# LED_KEYBOARD.net
KiCad netlist of a schematic drawn in Altium Designer
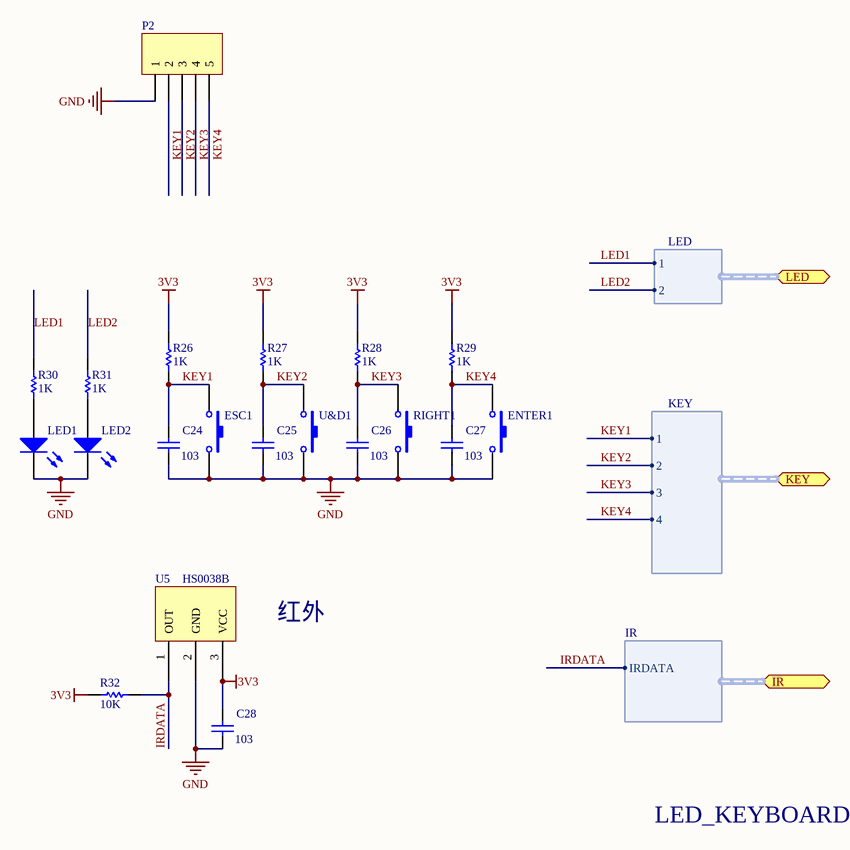
[diagram p0: LED_KEYBOARD.SchDoc]

(export (version "E")
  (design (tool "Eeschema 10.0.6"))
  (components
    (comp (ref "C24")
      (value "103")
      (footprint "RC0805")
      (description "Capacitor")
      (fields (field (name "Comment") "Cap") (field (name "PUBLISHER") "Altium Limited"))
      (libsource (lib "Miscellaneous Devices") (part "Cap"))
    )
    (comp (ref "C25")
      (value "103")
      (footprint "RC0805")
      (description "Capacitor")
      (fields (field (name "Comment") "Cap") (field (name "PUBLISHER") "Altium Limited"))
      (libsource (lib "Miscellaneous Devices") (part "Cap"))
    )
    (comp (ref "C26")
      (value "103")
      (footprint "RC0805")
      (description "Capacitor")
      (fields (field (name "Comment") "Cap") (field (name "PUBLISHER") "Altium Limited"))
      (libsource (lib "Miscellaneous Devices") (part "Cap"))
    )
    (comp (ref "C27")
      (value "103")
      (footprint "RC0805")
      (description "Capacitor")
      (fields (field (name "Comment") "Cap") (field (name "PUBLISHER") "Altium Limited"))
      (libsource (lib "Miscellaneous Devices") (part "Cap"))
    )
    (comp (ref "C28")
      (value "103")
      (footprint "RC0805")
      (description "Capacitor")
      (fields (field (name "Comment") "Cap") (field (name "PUBLISHER") "Altium Limited"))
      (libsource (lib "Miscellaneous Devices") (part "Cap"))
    )
    (comp (ref "ENTER1")
      (value "SW-PB")
      (footprint "KEY6*6(LARGE)")
      (description "Switch")
      (fields (field (name "PUBLISHER") "Altium Limited"))
      (libsource (lib "Miscellaneous Devices") (part "SW-PB"))
    )
    (comp (ref "ESC1")
      (value "SW-PB")
      (footprint "KEY6*6(LARGE)")
      (description "Switch")
      (fields (field (name "PUBLISHER") "Altium Limited"))
      (libsource (lib "Miscellaneous Devices") (part "SW-PB"))
    )
    (comp (ref "LED1")
      (value "LED0")
      (footprint "LED")
      (description "Typical INFRARED GaAs LED")
      (fields (field (name "PUBLISHER") "Altium Limited"))
      (libsource (lib "Miscellaneous Devices") (part "LED0"))
    )
    (comp (ref "LED2")
      (value "LED0")
      (footprint "LED")
      (description "Typical INFRARED GaAs LED")
      (fields (field (name "PUBLISHER") "Altium Limited"))
      (libsource (lib "Miscellaneous Devices") (part "LED0"))
    )
    (comp (ref "P2")
      (value "Header 5")
      (footprint "HDR1X5")
      (description "Header, 5-Pin")
      (fields (field (name "PUBLISHER") "Altium Limited"))
      (libsource (lib "Miscellaneous Connectors") (part "Header 5"))
    )
    (comp (ref "R26")
      (value "1K")
      (footprint "RC0805")
      (description "Resistor")
      (fields (field (name "Comment") "Res1") (field (name "PUBLISHER") "Altium Limited"))
      (libsource (lib "Miscellaneous Devices") (part "Res1"))
    )
    (comp (ref "R27")
      (value "1K")
      (footprint "RC0805")
      (description "Resistor")
      (fields (field (name "Comment") "Res1") (field (name "PUBLISHER") "Altium Limited"))
      (libsource (lib "Miscellaneous Devices") (part "Res1"))
    )
    (comp (ref "R28")
      (value "1K")
      (footprint "RC0805")
      (description "Resistor")
      (fields (field (name "Comment") "Res1") (field (name "PUBLISHER") "Altium Limited"))
      (libsource (lib "Miscellaneous Devices") (part "Res1"))
    )
    (comp (ref "R29")
      (value "1K")
      (footprint "RC0805")
      (description "Resistor")
      (fields (field (name "Comment") "Res1") (field (name "PUBLISHER") "Altium Limited"))
      (libsource (lib "Miscellaneous Devices") (part "Res1"))
    )
    (comp (ref "R30")
      (value "1K")
      (footprint "RC0805")
      (description "Resistor")
      (fields (field (name "Comment") "Res1") (field (name "PUBLISHER") "Altium Limited"))
      (libsource (lib "Miscellaneous Devices") (part "Res1"))
    )
    (comp (ref "R31")
      (value "1K")
      (footprint "RC0805")
      (description "Resistor")
      (fields (field (name "Comment") "Res1") (field (name "PUBLISHER") "Altium Limited"))
      (libsource (lib "Miscellaneous Devices") (part "Res1"))
    )
    (comp (ref "R32")
      (value "10K")
      (footprint "RC0805")
      (description "Resistor")
      (fields (field (name "Comment") "Res1") (field (name "PUBLISHER") "Altium Limited"))
      (libsource (lib "Miscellaneous Devices") (part "Res1"))
    )
    (comp (ref "RIGHT1")
      (value "SW-PB")
      (footprint "KEY6*6(LARGE)")
      (description "Switch")
      (fields (field (name "PUBLISHER") "Altium Limited"))
      (libsource (lib "Miscellaneous Devices") (part "SW-PB"))
    )
    (comp (ref "U&D1")
      (value "SW-PB")
      (footprint "KEY6*6(LARGE)")
      (description "Switch")
      (fields (field (name "PUBLISHER") "Altium Limited"))
      (libsource (lib "Miscellaneous Devices") (part "SW-PB"))
    )
    (comp (ref "U5") (value "HS0038B") (footprint "HS0038") (libsource (lib "STM32F103VE") (part "HS0038B")))
  )
  (nets
    (net (code "4") (name "/IRDATA") (class "Default")
      (node (ref "R32") (pin "2") (pinfunction "2_2") (pintype "passive"))
      (node (ref "U5") (pin "1") (pinfunction "OUT_1") (pintype "passive"))
    )
    (net (code "5") (name "/KEY1") (class "Default")
      (node (ref "C24") (pin "2") (pinfunction "2_2") (pintype "passive"))
      (node (ref "ESC1") (pin "1") (pinfunction "1_1") (pintype "passive"))
      (node (ref "P2") (pin "2") (pinfunction "2_2") (pintype "passive"))
      (node (ref "R26") (pin "2") (pinfunction "2_2") (pintype "passive"))
    )
    (net (code "6") (name "/KEY2") (class "Default")
      (node (ref "C25") (pin "2") (pinfunction "2_2") (pintype "passive"))
      (node (ref "P2") (pin "3") (pinfunction "3_3") (pintype "passive"))
      (node (ref "R27") (pin "2") (pinfunction "2_2") (pintype "passive"))
      (node (ref "U&D1") (pin "1") (pinfunction "1_1") (pintype "passive"))
    )
    (net (code "7") (name "/KEY3") (class "Default")
      (node (ref "C26") (pin "2") (pinfunction "2_2") (pintype "passive"))
      (node (ref "P2") (pin "4") (pinfunction "4_4") (pintype "passive"))
      (node (ref "R28") (pin "2") (pinfunction "2_2") (pintype "passive"))
      (node (ref "RIGHT1") (pin "1") (pinfunction "1_1") (pintype "passive"))
    )
    (net (code "8") (name "/KEY4") (class "Default")
      (node (ref "C27") (pin "2") (pinfunction "2_2") (pintype "passive"))
      (node (ref "ENTER1") (pin "1") (pinfunction "1_1") (pintype "passive"))
      (node (ref "P2") (pin "5") (pinfunction "5_5") (pintype "passive"))
      (node (ref "R29") (pin "2") (pinfunction "2_2") (pintype "passive"))
    )
    (net (code "9") (name "/LED1") (class "Default")
      (node (ref "R30") (pin "2") (pinfunction "2_2") (pintype "passive"))
    )
    (net (code "10") (name "/LED2") (class "Default")
      (node (ref "R31") (pin "2") (pinfunction "2_2") (pintype "passive"))
    )
    (net (code "14") (name "3V3") (class "Default")
      (node (ref "C28") (pin "2") (pinfunction "2_2") (pintype "passive"))
      (node (ref "R26") (pin "1") (pinfunction "1_1") (pintype "passive"))
      (node (ref "R27") (pin "1") (pinfunction "1_1") (pintype "passive"))
      (node (ref "R28") (pin "1") (pinfunction "1_1") (pintype "passive"))
      (node (ref "R29") (pin "1") (pinfunction "1_1") (pintype "passive"))
      (node (ref "R32") (pin "1") (pinfunction "1_1") (pintype "passive"))
      (node (ref "U5") (pin "3") (pinfunction "VCC_3") (pintype "passive"))
    )
    (net (code "15") (name "GND") (class "Default")
      (node (ref "C24") (pin "1") (pinfunction "1_1") (pintype "passive"))
      (node (ref "C25") (pin "1") (pinfunction "1_1") (pintype "passive"))
      (node (ref "C26") (pin "1") (pinfunction "1_1") (pintype "passive"))
      (node (ref "C27") (pin "1") (pinfunction "1_1") (pintype "passive"))
      (node (ref "C28") (pin "1") (pinfunction "1_1") (pintype "passive"))
      (node (ref "ENTER1") (pin "2") (pinfunction "2_2") (pintype "passive"))
      (node (ref "ESC1") (pin "2") (pinfunction "2_2") (pintype "passive"))
      (node (ref "LED1") (pin "2") (pinfunction "K_2") (pintype "passive"))
      (node (ref "LED2") (pin "2") (pinfunction "K_2") (pintype "passive"))
      (node (ref "P2") (pin "1") (pinfunction "1_1") (pintype "passive"))
      (node (ref "RIGHT1") (pin "2") (pinfunction "2_2") (pintype "passive"))
      (node (ref "U&D1") (pin "2") (pinfunction "2_2") (pintype "passive"))
      (node (ref "U5") (pin "2") (pinfunction "GND_2") (pintype "passive"))
    )
    (net (code "16") (name "Net-(LED1-A)") (class "Default")
      (node (ref "LED1") (pin "1") (pinfunction "A_1") (pintype "passive"))
      (node (ref "R30") (pin "1") (pinfunction "1_1") (pintype "passive"))
    )
    (net (code "17") (name "Net-(LED2-A)") (class "Default")
      (node (ref "LED2") (pin "1") (pinfunction "A_1") (pintype "passive"))
      (node (ref "R31") (pin "1") (pinfunction "1_1") (pintype "passive"))
    )
  )
)
